# Pressure_Sensor.net
KiCad netlist of a schematic drawn in Altium Designer
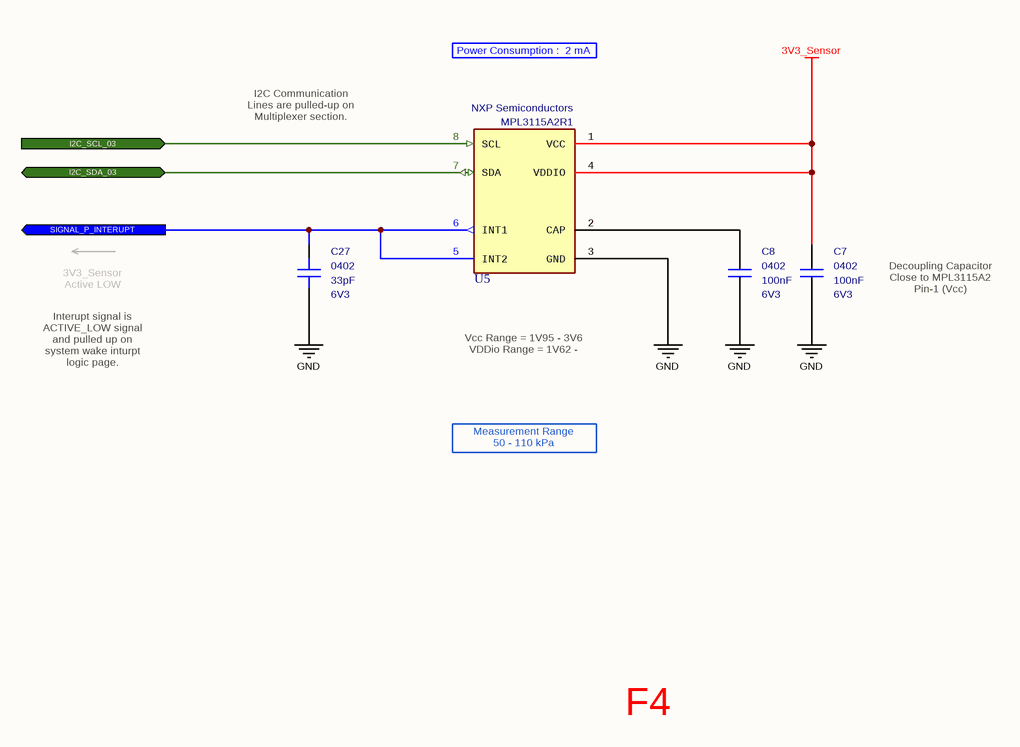
[diagram p0: Pressure Sensor.SchDoc]

(export (version "E")
  (design (tool "Eeschema 10.0.6"))
  (components
    (comp (ref "C7")
      (value "100nF")
      (footprint "CAPACITOR_0402")
      (description "Capacitor - 100nF [0402-6V3] (Ceramic)")
      (fields
        (field (name "MANUFACTURER_PART_NUMBER") "04026D104KAT4A")
        (field (name "MOUSER_PART_NUMBER") "581-04026D104KAT4A")
        (field (name "CASE") "0402")
        (field (name "VOLTAGE") "6V3")
      )
      (libsource (lib "Ovoo_Schematic") (part "Capacitor - 100nF [0402-6V3]"))
    )
    (comp (ref "C8")
      (value "100nF")
      (footprint "CAPACITOR_0402")
      (description "Capacitor - 100nF [0402-6V3] (Ceramic)")
      (fields
        (field (name "MANUFACTURER_PART_NUMBER") "04026D104KAT4A")
        (field (name "MOUSER_PART_NUMBER") "581-04026D104KAT4A")
        (field (name "CASE") "0402")
        (field (name "VOLTAGE") "6V3")
      )
      (libsource (lib "Ovoo_Schematic") (part "Capacitor - 100nF [0402-6V3]"))
    )
    (comp (ref "C27")
      (value "33pF")
      (footprint "CAPACITOR_0402")
      (description "Capacitor - 33pF [0402] (Ceramic)")
      (fields
        (field (name "MANUFACTURER_PART_NUMBER") "C0402C330J9RACAUTO")
        (field (name "MOUSER_PART_NUMBER") "80-C0402C330J9RAUTO")
        (field (name "CASE") "0402")
        (field (name "VOLTAGE") "6V3")
      )
      (libsource (lib "Ovoo_Schematic") (part "Capacitor - 33pF [0402-6V3]"))
    )
    (comp (ref "U5")
      (value "Board Mount Pressure Sensors")
      (footprint "MPL3115A2")
      (description "Board Mount Pressure Sensors I 2 C VERSION")
      (fields
        (field (name "MOUSER PART NUMBER") "841-MPL3115A2R1")
        (field (name "MANUFACTURER_PART_NUMBER") "MPL3115A2R1")
        (field (name "MANUFACTURER_NAME") "NXP Semiconductors")
      )
      (libsource (lib "Ovoo_Schematic") (part "IC - MPL3115A2R1"))
    )
  )
  (nets
    (net (code "1") (name "/I2C_SCL_03") (class "Default")
      (node (ref "U5") (pin "8") (pinfunction "SCL_8") (pintype "input"))
    )
    (net (code "2") (name "/I2C_SDA_03") (class "Default")
      (node (ref "U5") (pin "7") (pinfunction "SDA_7") (pintype "bidirectional"))
    )
    (net (code "3") (name "/SIGNAL_P_INTERUPT") (class "Default")
      (node (ref "C27") (pin "2") (pinfunction "2_2") (pintype "passive"))
      (node (ref "U5") (pin "5") (pinfunction "INT2_5") (pintype "passive"))
      (node (ref "U5") (pin "6") (pinfunction "INT1_6") (pintype "output"))
    )
    (net (code "4") (name "3V3_Sensor") (class "Default")
      (node (ref "C7") (pin "2") (pinfunction "2_2") (pintype "passive"))
      (node (ref "U5") (pin "1") (pinfunction "VCC_1") (pintype "power_in"))
      (node (ref "U5") (pin "4") (pinfunction "VDDIO_4") (pintype "power_in"))
    )
    (net (code "5") (name "GND") (class "Default")
      (node (ref "C27") (pin "1") (pinfunction "1_1") (pintype "passive"))
      (node (ref "C7") (pin "1") (pinfunction "1_1") (pintype "passive"))
      (node (ref "C8") (pin "1") (pinfunction "1_1") (pintype "passive"))
      (node (ref "U5") (pin "3") (pinfunction "GND_3") (pintype "power_in"))
    )
    (net (code "6") (name "Net-(U5-CAP)") (class "Default")
      (node (ref "C8") (pin "2") (pinfunction "2_2") (pintype "passive"))
      (node (ref "U5") (pin "2") (pinfunction "CAP_2") (pintype "passive"))
    )
  )
)
